# USB.net
KiCad netlist of a schematic drawn in Altium Designer
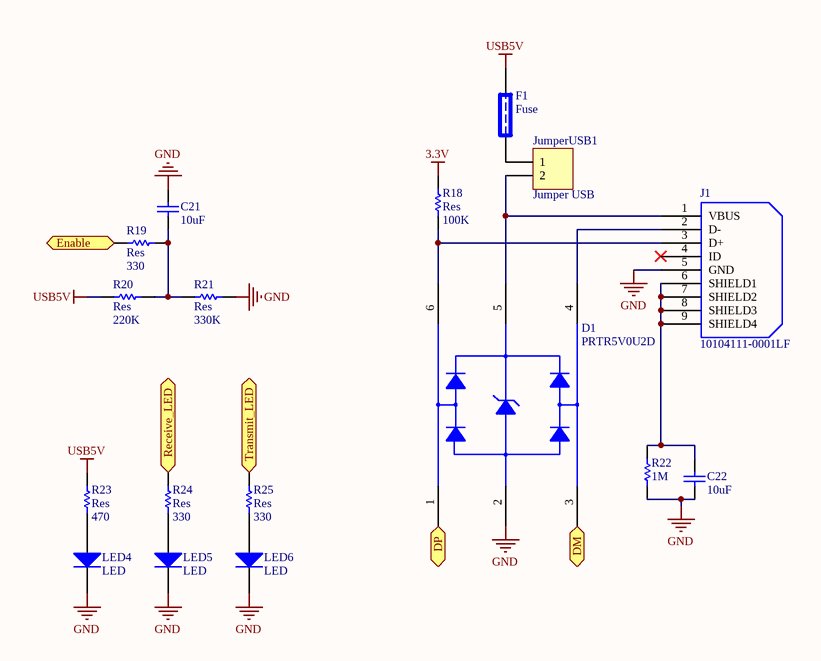
[diagram p0: USB.SchDoc]

(export (version "E")
  (design (tool "Eeschema 10.0.6"))
  (components
    (comp (ref "C21")
      (value "10uF")
      (footprint "2012[0805]")
      (description "Capacitor")
      (fields (field (name "Comment") "Cap_UP") (field (name "PUBLISHER") "Altium Limited"))
      (libsource (lib "KN2CLib") (part "Cap_UP"))
    )
    (comp (ref "C22")
      (value "10uF")
      (footprint "2012[0805]")
      (description "Capacitor")
      (fields (field (name "Comment") "Cap_UP") (field (name "PUBLISHER") "Altium Limited"))
      (libsource (lib "KN2CLib") (part "Cap_UP"))
    )
    (comp (ref "D1")
      (value "PRTR5V0U2D")
      (footprint "PRTR5V0U2D")
      (description "Double rail-to-rail USB ESD protection diode")
      (fields (field (name "MANUFACTURER") "Philips") (field (name "MPN") "PRTR5V0U2X"))
      (libsource (lib "KN2CLib") (part "PRTR5V0U2D"))
    )
    (comp (ref "F1")
      (value "Fuse")
      (footprint "3216[1206]")
      (fields (field (name "PUBLISHER") "Altium Limited"))
      (libsource (lib "KN2CLib") (part "Fuse"))
    )
    (comp (ref "J1")
      (value "10104111-0001LF")
      (footprint "USB_MINI")
      (description "Micro USB AB Connector")
      (fields (field (name "MANUFACTURER") "FCI") (field (name "Comment") "USB_AB"))
      (libsource (lib "KN2CLib") (part "USB_AB"))
    )
    (comp (ref "JumperUSB1")
      (value "Jumper USB")
      (footprint "HDR1X2")
      (description "Header, 2-Pin")
      (fields (field (name "PUBLISHER") "Altium Limited"))
      (libsource (lib "Miscellaneous Connectors") (part "Header 2"))
    )
    (comp (ref "LED4")
      (value "LED")
      (footprint "2012[0805]")
      (description "1 Amp General Purpose Rectifier")
      (fields (field (name "PUBLISHER") "Altium Limited"))
      (libsource (lib "KN2CLib") (part "Diode"))
    )
    (comp (ref "LED5")
      (value "LED")
      (footprint "2012[0805]")
      (description "1 Amp General Purpose Rectifier")
      (fields (field (name "PUBLISHER") "Altium Limited"))
      (libsource (lib "KN2CLib") (part "Diode"))
    )
    (comp (ref "LED6")
      (value "LED")
      (footprint "2012[0805]")
      (description "1 Amp General Purpose Rectifier")
      (fields (field (name "PUBLISHER") "Altium Limited"))
      (libsource (lib "KN2CLib") (part "Diode"))
    )
    (comp (ref "R18")
      (value "Res")
      (footprint "2012[0805]")
      (description "Semiconductor Resistor")
      (fields (field (name "ALTIUM_VALUE") "100K") (field (name "PUBLISHER") "Altium Limited"))
      (libsource (lib "KN2CLib") (part "Res"))
    )
    (comp (ref "R19")
      (value "Res")
      (footprint "2012[0805]")
      (description "Semiconductor Resistor")
      (fields (field (name "ALTIUM_VALUE") "330") (field (name "PUBLISHER") "Altium Limited"))
      (libsource (lib "KN2CLib") (part "Res"))
    )
    (comp (ref "R20")
      (value "Res")
      (footprint "2012[0805]")
      (description "Semiconductor Resistor")
      (fields (field (name "ALTIUM_VALUE") "220K") (field (name "PUBLISHER") "Altium Limited"))
      (libsource (lib "KN2CLib") (part "Res"))
    )
    (comp (ref "R21")
      (value "Res")
      (footprint "2012[0805]")
      (description "Semiconductor Resistor")
      (fields (field (name "ALTIUM_VALUE") "330K") (field (name "PUBLISHER") "Altium Limited"))
      (libsource (lib "KN2CLib") (part "Res"))
    )
    (comp (ref "R22")
      (value "1M")
      (footprint "2012[0805]")
      (description "Semiconductor Resistor")
      (fields (field (name "PUBLISHER") "Altium Limited"))
      (libsource (lib "KN2CLib") (part "Res"))
    )
    (comp (ref "R23")
      (value "Res")
      (footprint "2012[0805]")
      (description "Semiconductor Resistor")
      (fields (field (name "ALTIUM_VALUE") "470") (field (name "PUBLISHER") "Altium Limited"))
      (libsource (lib "KN2CLib") (part "Res"))
    )
    (comp (ref "R24")
      (value "Res")
      (footprint "2012[0805]")
      (description "Semiconductor Resistor")
      (fields (field (name "ALTIUM_VALUE") "330") (field (name "PUBLISHER") "Altium Limited"))
      (libsource (lib "KN2CLib") (part "Res"))
    )
    (comp (ref "R25")
      (value "Res")
      (footprint "2012[0805]")
      (description "Semiconductor Resistor")
      (fields (field (name "ALTIUM_VALUE") "330") (field (name "PUBLISHER") "Altium Limited"))
      (libsource (lib "KN2CLib") (part "Res"))
    )
  )
  (nets
    (net (code "1") (name "/DM") (class "Default")
      (node (ref "D1") (pin "3") (pinfunction "I/O2_3") (pintype "passive"))
    )
    (net (code "2") (name "/DP") (class "Default")
      (node (ref "D1") (pin "1") (pinfunction "I/O_1_1") (pintype "passive"))
    )
    (net (code "3") (name "/Enable") (class "Default")
      (node (ref "R19") (pin "1") (pinfunction "1_1") (pintype "passive"))
    )
    (net (code "4") (name "/Receive_LED") (class "Default")
      (node (ref "R24") (pin "1") (pinfunction "1_1") (pintype "passive"))
    )
    (net (code "5") (name "/Transmit_LED") (class "Default")
      (node (ref "R25") (pin "1") (pinfunction "1_1") (pintype "passive"))
    )
    (net (code "6") (name "3.3V") (class "Default")
      (node (ref "R18") (pin "1") (pinfunction "1_1") (pintype "passive"))
    )
    (net (code "7") (name "GND") (class "Default")
      (node (ref "C21") (pin "1") (pinfunction "1_1") (pintype "passive"))
      (node (ref "C22") (pin "1") (pinfunction "1_1") (pintype "passive"))
      (node (ref "D1") (pin "2") (pinfunction "GND_2") (pintype "passive"))
      (node (ref "J1") (pin "5") (pinfunction "GND_5") (pintype "passive"))
      (node (ref "LED4") (pin "2") (pinfunction "K_2") (pintype "passive"))
      (node (ref "LED5") (pin "2") (pinfunction "K_2") (pintype "passive"))
      (node (ref "LED6") (pin "2") (pinfunction "K_2") (pintype "passive"))
      (node (ref "R21") (pin "2") (pinfunction "2_2") (pintype "passive"))
      (node (ref "R22") (pin "1") (pinfunction "1_1") (pintype "passive"))
    )
    (net (code "8") (name "Net-(C21-Pad2)") (class "Default")
      (node (ref "C21") (pin "2") (pinfunction "2_2") (pintype "passive"))
      (node (ref "R19") (pin "2") (pinfunction "2_2") (pintype "passive"))
      (node (ref "R20") (pin "2") (pinfunction "2_2") (pintype "passive"))
      (node (ref "R21") (pin "1") (pinfunction "1_1") (pintype "passive"))
    )
    (net (code "9") (name "Net-(D1-I{slash}O1)") (class "Default")
      (node (ref "D1") (pin "6") (pinfunction "I/O1_6") (pintype "passive"))
      (node (ref "J1") (pin "3") (pinfunction "D+_3") (pintype "passive"))
      (node (ref "R18") (pin "2") (pinfunction "2_2") (pintype "passive"))
    )
    (net (code "10") (name "Net-(D1-VCC)") (class "Default")
      (node (ref "D1") (pin "5") (pinfunction "VCC_5") (pintype "passive"))
      (node (ref "J1") (pin "1") (pinfunction "VBUS_1") (pintype "passive"))
      (node (ref "JumperUSB1") (pin "2") (pinfunction "2_2") (pintype "passive"))
    )
    (net (code "11") (name "Net-(F1-Pad1)") (class "Default")
      (node (ref "F1") (pin "1") (pinfunction "1_1") (pintype "passive"))
      (node (ref "JumperUSB1") (pin "1") (pinfunction "1_1") (pintype "passive"))
    )
    (net (code "12") (name "Net-(J1-D-)") (class "Default")
      (node (ref "D1") (pin "4") (pinfunction "I/O2_4") (pintype "passive"))
      (node (ref "J1") (pin "2") (pinfunction "D-_2") (pintype "passive"))
    )
    (net (code "13") (name "Net-(J1-SHIELD1)") (class "Default")
      (node (ref "C22") (pin "2") (pinfunction "2_2") (pintype "passive"))
      (node (ref "J1") (pin "6") (pinfunction "SHIELD1_6") (pintype "passive"))
      (node (ref "J1") (pin "7") (pinfunction "SHIELD2_7") (pintype "passive"))
      (node (ref "J1") (pin "8") (pinfunction "SHIELD3_8") (pintype "passive"))
      (node (ref "J1") (pin "9") (pinfunction "SHIELD4_9") (pintype "passive"))
      (node (ref "R22") (pin "2") (pinfunction "2_2") (pintype "passive"))
    )
    (net (code "14") (name "Net-(LED4-A)") (class "Default")
      (node (ref "LED4") (pin "1") (pinfunction "A_1") (pintype "passive"))
      (node (ref "R23") (pin "2") (pinfunction "2_2") (pintype "passive"))
    )
    (net (code "15") (name "Net-(LED5-A)") (class "Default")
      (node (ref "LED5") (pin "1") (pinfunction "A_1") (pintype "passive"))
      (node (ref "R24") (pin "2") (pinfunction "2_2") (pintype "passive"))
    )
    (net (code "16") (name "Net-(LED6-A)") (class "Default")
      (node (ref "LED6") (pin "1") (pinfunction "A_1") (pintype "passive"))
      (node (ref "R25") (pin "2") (pinfunction "2_2") (pintype "passive"))
    )
    (net (code "17") (name "USB5V") (class "Default")
      (node (ref "F1") (pin "2") (pinfunction "2_2") (pintype "passive"))
      (node (ref "R20") (pin "1") (pinfunction "1_1") (pintype "passive"))
      (node (ref "R23") (pin "1") (pinfunction "1_1") (pintype "passive"))
    )
    (net (code "18") (name "unconnected-(J1-ID-Pad4)") (class "Default")
      (node (ref "J1") (pin "4") (pinfunction "ID_4") (pintype "passive+no_connect"))
    )
  )
)
